# main_PCA9685.net
KiCad netlist of a schematic drawn in EAGLE
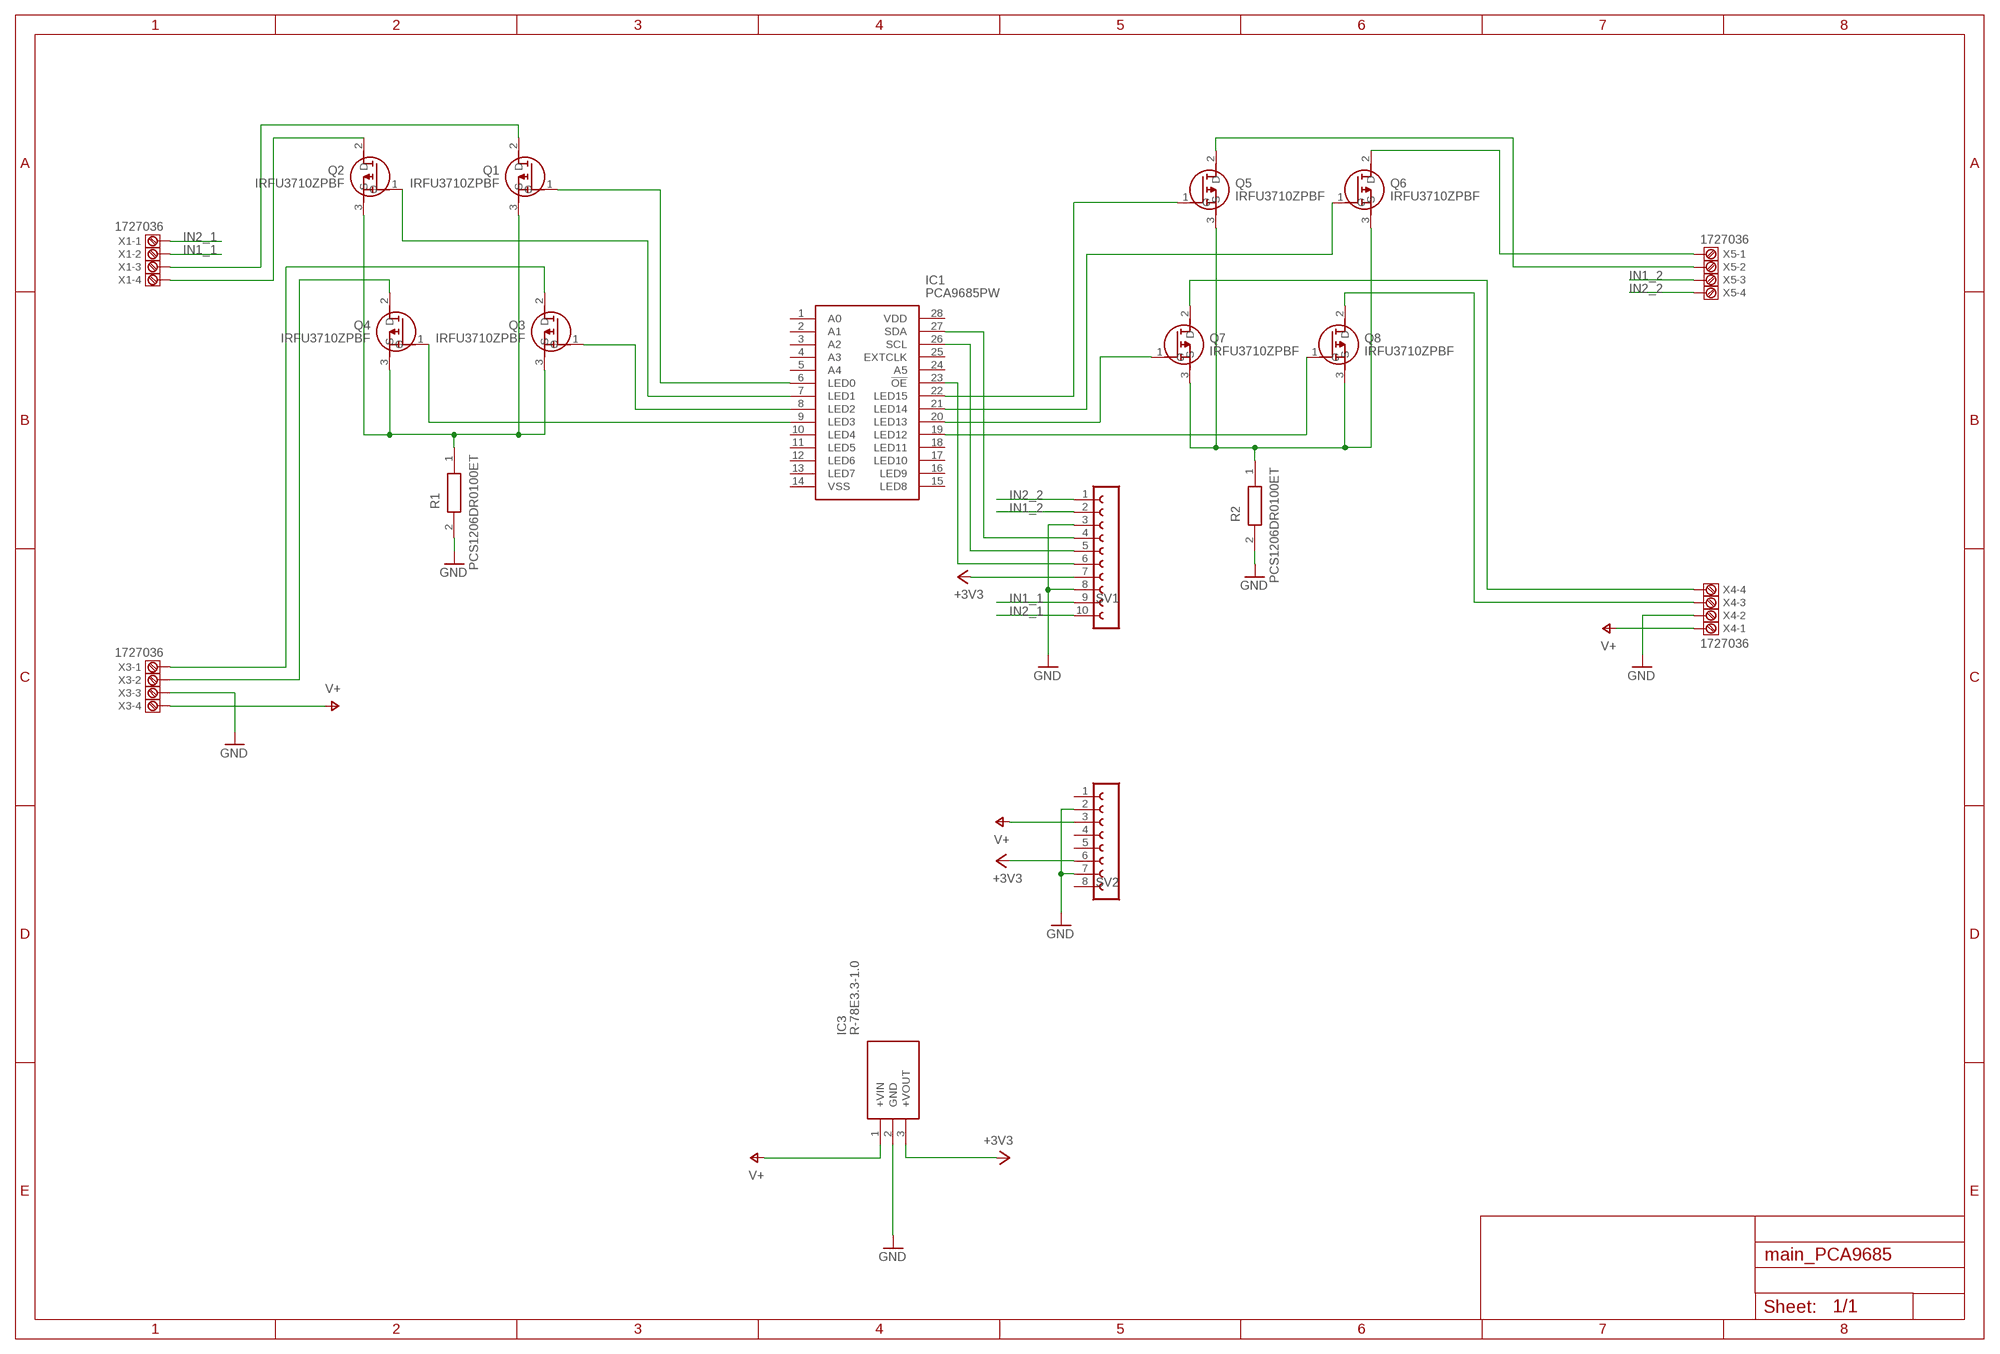
[diagram p0: schematic, sheet 1]

(export (version "E")
  (design (tool "Eeschema 10.0.6"))
  (components
    (comp (ref "IC1")
      (value "PCA9685PW")
      (footprint "eagle-import:SOP65P640X110-28N")
      (libsource (lib "eagle-import") (part "PCA9685PW"))
    )
    (comp (ref "IC3")
      (value "R-78E3.3-1.0")
      (footprint "eagle-import:R78E3310")
      (fields (field (name "MOUSER_PART_NUMBER") "919-R-78E3.3-1.0"))
      (libsource (lib "eagle-import") (part "R-78E3.3-1.0"))
    )
    (comp (ref "Q1")
      (value "IRFU3710ZPBF")
      (footprint "eagle-import:TO229P239X654X978-3P")
      (fields (field (name "MOUSER_PART_NUMBER") "942-IRFU3710ZPBF"))
      (libsource (lib "eagle-import") (part "IRFU3710ZPBF"))
    )
    (comp (ref "Q2")
      (value "IRFU3710ZPBF")
      (footprint "eagle-import:TO229P239X654X978-3P")
      (fields (field (name "MOUSER_PART_NUMBER") "942-IRFU3710ZPBF"))
      (libsource (lib "eagle-import") (part "IRFU3710ZPBF"))
    )
    (comp (ref "Q3")
      (value "IRFU3710ZPBF")
      (footprint "eagle-import:TO229P239X654X978-3P")
      (fields (field (name "MOUSER_PART_NUMBER") "942-IRFU3710ZPBF"))
      (libsource (lib "eagle-import") (part "IRFU3710ZPBF"))
    )
    (comp (ref "Q4")
      (value "IRFU3710ZPBF")
      (footprint "eagle-import:TO229P239X654X978-3P")
      (fields (field (name "MOUSER_PART_NUMBER") "942-IRFU3710ZPBF"))
      (libsource (lib "eagle-import") (part "IRFU3710ZPBF"))
    )
    (comp (ref "Q5")
      (value "IRFU3710ZPBF")
      (footprint "eagle-import:TO229P239X654X978-3P")
      (fields (field (name "MOUSER_PART_NUMBER") "942-IRFU3710ZPBF"))
      (libsource (lib "eagle-import") (part "IRFU3710ZPBF"))
    )
    (comp (ref "Q6")
      (value "IRFU3710ZPBF")
      (footprint "eagle-import:TO229P239X654X978-3P")
      (fields (field (name "MOUSER_PART_NUMBER") "942-IRFU3710ZPBF"))
      (libsource (lib "eagle-import") (part "IRFU3710ZPBF"))
    )
    (comp (ref "Q7")
      (value "IRFU3710ZPBF")
      (footprint "eagle-import:TO229P239X654X978-3P")
      (fields (field (name "MOUSER_PART_NUMBER") "942-IRFU3710ZPBF"))
      (libsource (lib "eagle-import") (part "IRFU3710ZPBF"))
    )
    (comp (ref "Q8")
      (value "IRFU3710ZPBF")
      (footprint "eagle-import:TO229P239X654X978-3P")
      (fields (field (name "MOUSER_PART_NUMBER") "942-IRFU3710ZPBF"))
      (libsource (lib "eagle-import") (part "IRFU3710ZPBF"))
    )
    (comp (ref "R1")
      (value "PCS1206DR0100ET")
      (footprint "eagle-import:RESC3216X68N")
      (fields (field (name "MOUSER_PART_NUMBER") "588-PCS1206DR0100ET"))
      (libsource (lib "eagle-import") (part "PCS1206DR0100ET"))
    )
    (comp (ref "R2")
      (value "PCS1206DR0100ET")
      (footprint "eagle-import:RESC3216X68N")
      (fields (field (name "MOUSER_PART_NUMBER") "588-PCS1206DR0100ET"))
      (libsource (lib "eagle-import") (part "PCS1206DR0100ET"))
    )
    (comp (ref "SV1")
      (value "FE10-1")
      (footprint "eagle-import:FE10")
      (libsource (lib "eagle-import") (part "FE10-1"))
    )
    (comp (ref "SV2")
      (value "FE08-1")
      (footprint "eagle-import:FE08")
      (libsource (lib "eagle-import") (part "FE08-1"))
    )
    (comp (ref "X1")
      (value "1727036")
      (footprint "eagle-import:1727036")
      (fields (field (name "MF") "FARNELL"))
      (libsource (lib "eagle-import") (part "1727036"))
    )
    (comp (ref "X3")
      (value "1727036")
      (footprint "eagle-import:1727036")
      (fields (field (name "MF") "FARNELL"))
      (libsource (lib "eagle-import") (part "1727036"))
    )
    (comp (ref "X4")
      (value "1727036")
      (footprint "eagle-import:1727036")
      (fields (field (name "MF") "FARNELL"))
      (libsource (lib "eagle-import") (part "1727036"))
    )
    (comp (ref "X5")
      (value "1727036")
      (footprint "eagle-import:1727036")
      (fields (field (name "MF") "FARNELL"))
      (libsource (lib "eagle-import") (part "1727036"))
    )
  )
  (nets
    (net (code "1") (name "+3V3") (class "Default")
      (node (ref "IC3") (pin "3") (pinfunction "+VOUT_3") (pintype "bidirectional"))
      (node (ref "SV1") (pin "7") (pinfunction "7_7") (pintype "passive"))
      (node (ref "SV2") (pin "6") (pinfunction "6_6") (pintype "passive"))
    )
    (net (code "2") (name "/IN1_1") (class "Default")
      (node (ref "SV1") (pin "9") (pinfunction "9_9") (pintype "passive"))
      (node (ref "X1") (pin "2") (pinfunction "1_2") (pintype "passive"))
    )
    (net (code "3") (name "/IN1_2") (class "Default")
      (node (ref "SV1") (pin "2") (pinfunction "2_2") (pintype "passive"))
      (node (ref "X5") (pin "3") (pinfunction "1_3") (pintype "passive"))
    )
    (net (code "4") (name "/IN2_1") (class "Default")
      (node (ref "SV1") (pin "10") (pinfunction "10_10") (pintype "passive"))
      (node (ref "X1") (pin "1") (pinfunction "1_1") (pintype "passive"))
    )
    (net (code "5") (name "/IN2_2") (class "Default")
      (node (ref "SV1") (pin "1") (pinfunction "1_1") (pintype "passive"))
      (node (ref "X5") (pin "4") (pinfunction "1_4") (pintype "passive"))
    )
    (net (code "6") (name "GND") (class "Default")
      (node (ref "IC3") (pin "2") (pinfunction "GND_2") (pintype "bidirectional"))
      (node (ref "R1") (pin "2") (pinfunction "2_2") (pintype "bidirectional"))
      (node (ref "R2") (pin "2") (pinfunction "2_2") (pintype "bidirectional"))
      (node (ref "SV1") (pin "3") (pinfunction "3_3") (pintype "passive"))
      (node (ref "SV1") (pin "8") (pinfunction "8_8") (pintype "passive"))
      (node (ref "SV2") (pin "2") (pinfunction "2_2") (pintype "passive"))
      (node (ref "SV2") (pin "7") (pinfunction "7_7") (pintype "passive"))
      (node (ref "X3") (pin "3") (pinfunction "1_3") (pintype "passive"))
      (node (ref "X4") (pin "2") (pinfunction "1_2") (pintype "passive"))
    )
    (net (code "7") (name "Net-(IC1-LED0)") (class "Default")
      (node (ref "IC1") (pin "6") (pinfunction "LED0_6") (pintype "bidirectional"))
      (node (ref "Q1") (pin "1") (pinfunction "G_1") (pintype "bidirectional"))
    )
    (net (code "8") (name "Net-(IC1-LED1)") (class "Default")
      (node (ref "IC1") (pin "7") (pinfunction "LED1_7") (pintype "bidirectional"))
      (node (ref "Q2") (pin "1") (pinfunction "G_1") (pintype "bidirectional"))
    )
    (net (code "9") (name "Net-(IC1-LED2)") (class "Default")
      (node (ref "IC1") (pin "8") (pinfunction "LED2_8") (pintype "bidirectional"))
      (node (ref "Q3") (pin "1") (pinfunction "G_1") (pintype "bidirectional"))
    )
    (net (code "10") (name "Net-(IC1-LED3)") (class "Default")
      (node (ref "IC1") (pin "9") (pinfunction "LED3_9") (pintype "bidirectional"))
      (node (ref "Q4") (pin "1") (pinfunction "G_1") (pintype "bidirectional"))
    )
    (net (code "11") (name "Net-(IC1-LED12)") (class "Default")
      (node (ref "IC1") (pin "19") (pinfunction "LED12_19") (pintype "bidirectional"))
      (node (ref "Q8") (pin "1") (pinfunction "G_1") (pintype "bidirectional"))
    )
    (net (code "12") (name "Net-(IC1-LED13)") (class "Default")
      (node (ref "IC1") (pin "20") (pinfunction "LED13_20") (pintype "bidirectional"))
      (node (ref "Q7") (pin "1") (pinfunction "G_1") (pintype "bidirectional"))
    )
    (net (code "13") (name "Net-(IC1-LED14)") (class "Default")
      (node (ref "IC1") (pin "21") (pinfunction "LED14_21") (pintype "bidirectional"))
      (node (ref "Q6") (pin "1") (pinfunction "G_1") (pintype "bidirectional"))
    )
    (net (code "14") (name "Net-(IC1-LED15)") (class "Default")
      (node (ref "IC1") (pin "22") (pinfunction "LED15_22") (pintype "bidirectional"))
      (node (ref "Q5") (pin "1") (pinfunction "G_1") (pintype "bidirectional"))
    )
    (net (code "15") (name "Net-(IC1-SCL)") (class "Default")
      (node (ref "IC1") (pin "26") (pinfunction "SCL_26") (pintype "bidirectional"))
      (node (ref "SV1") (pin "5") (pinfunction "5_5") (pintype "passive"))
    )
    (net (code "16") (name "Net-(IC1-SDA)") (class "Default")
      (node (ref "IC1") (pin "27") (pinfunction "SDA_27") (pintype "bidirectional"))
      (node (ref "SV1") (pin "4") (pinfunction "4_4") (pintype "passive"))
    )
    (net (code "17") (name "Net-(IC1-~{OE})") (class "Default")
      (node (ref "IC1") (pin "23") (pinfunction "~{OE}_23") (pintype "bidirectional"))
      (node (ref "SV1") (pin "6") (pinfunction "6_6") (pintype "passive"))
    )
    (net (code "18") (name "Net-(Q1-D)") (class "Default")
      (node (ref "Q1") (pin "2") (pinfunction "D_2") (pintype "bidirectional"))
      (node (ref "X1") (pin "3") (pinfunction "1_3") (pintype "passive"))
    )
    (net (code "19") (name "Net-(Q1-S)") (class "Default")
      (node (ref "Q1") (pin "3") (pinfunction "S_3") (pintype "bidirectional"))
      (node (ref "Q2") (pin "3") (pinfunction "S_3") (pintype "bidirectional"))
      (node (ref "Q3") (pin "3") (pinfunction "S_3") (pintype "bidirectional"))
      (node (ref "Q4") (pin "3") (pinfunction "S_3") (pintype "bidirectional"))
      (node (ref "R1") (pin "1") (pinfunction "1_1") (pintype "bidirectional"))
    )
    (net (code "20") (name "Net-(Q2-D)") (class "Default")
      (node (ref "Q2") (pin "2") (pinfunction "D_2") (pintype "bidirectional"))
      (node (ref "X1") (pin "4") (pinfunction "1_4") (pintype "passive"))
    )
    (net (code "21") (name "Net-(Q3-D)") (class "Default")
      (node (ref "Q3") (pin "2") (pinfunction "D_2") (pintype "bidirectional"))
      (node (ref "X3") (pin "1") (pinfunction "1_1") (pintype "passive"))
    )
    (net (code "22") (name "Net-(Q4-D)") (class "Default")
      (node (ref "Q4") (pin "2") (pinfunction "D_2") (pintype "bidirectional"))
      (node (ref "X3") (pin "2") (pinfunction "1_2") (pintype "passive"))
    )
    (net (code "23") (name "Net-(Q5-D)") (class "Default")
      (node (ref "Q5") (pin "2") (pinfunction "D_2") (pintype "bidirectional"))
      (node (ref "X5") (pin "2") (pinfunction "1_2") (pintype "passive"))
    )
    (net (code "24") (name "Net-(Q5-S)") (class "Default")
      (node (ref "Q5") (pin "3") (pinfunction "S_3") (pintype "bidirectional"))
      (node (ref "Q6") (pin "3") (pinfunction "S_3") (pintype "bidirectional"))
      (node (ref "Q7") (pin "3") (pinfunction "S_3") (pintype "bidirectional"))
      (node (ref "Q8") (pin "3") (pinfunction "S_3") (pintype "bidirectional"))
      (node (ref "R2") (pin "1") (pinfunction "1_1") (pintype "bidirectional"))
    )
    (net (code "25") (name "Net-(Q6-D)") (class "Default")
      (node (ref "Q6") (pin "2") (pinfunction "D_2") (pintype "bidirectional"))
      (node (ref "X5") (pin "1") (pinfunction "1_1") (pintype "passive"))
    )
    (net (code "26") (name "Net-(Q7-D)") (class "Default")
      (node (ref "Q7") (pin "2") (pinfunction "D_2") (pintype "bidirectional"))
      (node (ref "X4") (pin "4") (pinfunction "1_4") (pintype "passive"))
    )
    (net (code "27") (name "Net-(Q8-D)") (class "Default")
      (node (ref "Q8") (pin "2") (pinfunction "D_2") (pintype "bidirectional"))
      (node (ref "X4") (pin "3") (pinfunction "1_3") (pintype "passive"))
    )
    (net (code "28") (name "V+") (class "Default")
      (node (ref "IC3") (pin "1") (pinfunction "+VIN_1") (pintype "bidirectional"))
      (node (ref "SV2") (pin "3") (pinfunction "3_3") (pintype "passive"))
      (node (ref "X3") (pin "4") (pinfunction "1_4") (pintype "passive"))
      (node (ref "X4") (pin "1") (pinfunction "1_1") (pintype "passive"))
    )
    (net (code "29") (name "unconnected-(IC1-A0-Pad1)") (class "Default")
      (node (ref "IC1") (pin "1") (pinfunction "A0_1") (pintype "bidirectional"))
    )
    (net (code "30") (name "unconnected-(IC1-A1-Pad2)") (class "Default")
      (node (ref "IC1") (pin "2") (pinfunction "A1_2") (pintype "bidirectional"))
    )
    (net (code "31") (name "unconnected-(IC1-A2-Pad3)") (class "Default")
      (node (ref "IC1") (pin "3") (pinfunction "A2_3") (pintype "bidirectional"))
    )
    (net (code "32") (name "unconnected-(IC1-A3-Pad4)") (class "Default")
      (node (ref "IC1") (pin "4") (pinfunction "A3_4") (pintype "bidirectional"))
    )
    (net (code "33") (name "unconnected-(IC1-A4-Pad5)") (class "Default")
      (node (ref "IC1") (pin "5") (pinfunction "A4_5") (pintype "bidirectional"))
    )
    (net (code "34") (name "unconnected-(IC1-A5-Pad24)") (class "Default")
      (node (ref "IC1") (pin "24") (pinfunction "A5_24") (pintype "bidirectional"))
    )
    (net (code "35") (name "unconnected-(IC1-EXTCLK-Pad25)") (class "Default")
      (node (ref "IC1") (pin "25") (pinfunction "EXTCLK_25") (pintype "bidirectional"))
    )
    (net (code "36") (name "unconnected-(IC1-LED4-Pad10)") (class "Default")
      (node (ref "IC1") (pin "10") (pinfunction "LED4_10") (pintype "bidirectional"))
    )
    (net (code "37") (name "unconnected-(IC1-LED5-Pad11)") (class "Default")
      (node (ref "IC1") (pin "11") (pinfunction "LED5_11") (pintype "bidirectional"))
    )
    (net (code "38") (name "unconnected-(IC1-LED6-Pad12)") (class "Default")
      (node (ref "IC1") (pin "12") (pinfunction "LED6_12") (pintype "bidirectional"))
    )
    (net (code "39") (name "unconnected-(IC1-LED7-Pad13)") (class "Default")
      (node (ref "IC1") (pin "13") (pinfunction "LED7_13") (pintype "bidirectional"))
    )
    (net (code "40") (name "unconnected-(IC1-LED8-Pad15)") (class "Default")
      (node (ref "IC1") (pin "15") (pinfunction "LED8_15") (pintype "bidirectional"))
    )
    (net (code "41") (name "unconnected-(IC1-LED9-Pad16)") (class "Default")
      (node (ref "IC1") (pin "16") (pinfunction "LED9_16") (pintype "bidirectional"))
    )
    (net (code "42") (name "unconnected-(IC1-LED10-Pad17)") (class "Default")
      (node (ref "IC1") (pin "17") (pinfunction "LED10_17") (pintype "bidirectional"))
    )
    (net (code "43") (name "unconnected-(IC1-LED11-Pad18)") (class "Default")
      (node (ref "IC1") (pin "18") (pinfunction "LED11_18") (pintype "bidirectional"))
    )
    (net (code "44") (name "unconnected-(IC1-VDD-Pad28)") (class "Default")
      (node (ref "IC1") (pin "28") (pinfunction "VDD_28") (pintype "bidirectional"))
    )
    (net (code "45") (name "unconnected-(IC1-VSS-Pad14)") (class "Default")
      (node (ref "IC1") (pin "14") (pinfunction "VSS_14") (pintype "bidirectional"))
    )
    (net (code "46") (name "unconnected-(SV2-Pad1)") (class "Default")
      (node (ref "SV2") (pin "1") (pinfunction "1_1") (pintype "passive"))
    )
    (net (code "47") (name "unconnected-(SV2-Pad4)") (class "Default")
      (node (ref "SV2") (pin "4") (pinfunction "4_4") (pintype "passive"))
    )
    (net (code "48") (name "unconnected-(SV2-Pad5)") (class "Default")
      (node (ref "SV2") (pin "5") (pinfunction "5_5") (pintype "passive"))
    )
    (net (code "49") (name "unconnected-(SV2-Pad8)") (class "Default")
      (node (ref "SV2") (pin "8") (pinfunction "8_8") (pintype "passive"))
    )
  )
)
